# CooperBuffer.net
KiCad netlist of a schematic drawn in EAGLE
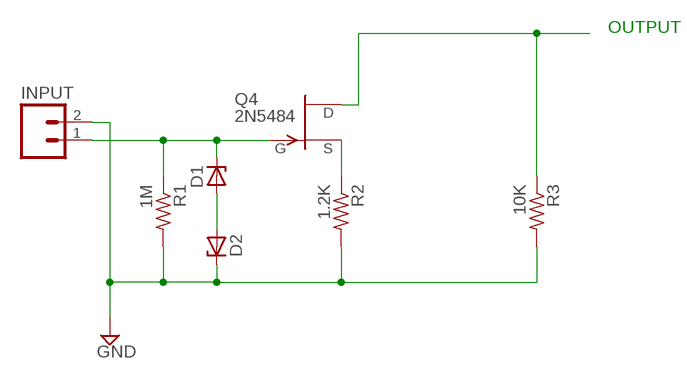
[diagram p0: schematic, sheet 1]

(export (version "E")
  (design (tool "Eeschema 10.0.6"))
  (components
    (comp (ref "D1")
      (value "1N821")
      (footprint "eagle-import:DO35Z10")
      (libsource (lib "eagle-import") (part "1N821"))
    )
    (comp (ref "D2")
      (value "1N821")
      (footprint "eagle-import:DO35Z10")
      (libsource (lib "eagle-import") (part "1N821"))
    )
    (comp (ref "INPUT")
      (value "M02LOCK")
      (footprint "eagle-import:1X02_LOCK")
      (libsource (lib "eagle-import") (part "M02LOCK"))
    )
    (comp (ref "Q4")
      (value "2N5484")
      (footprint "eagle-import:TO92-")
      (libsource (lib "eagle-import") (part "?5482N4"))
    )
    (comp (ref "R1")
      (value "1M")
      (footprint "eagle-import:VMTA55")
      (libsource (lib "eagle-import") (part "R-US_VMTA55"))
    )
    (comp (ref "R2")
      (value "1.2K")
      (footprint "eagle-import:VMTA55")
      (libsource (lib "eagle-import") (part "R-US_VMTA55"))
    )
    (comp (ref "R3")
      (value "10K")
      (footprint "eagle-import:VMTA55")
      (libsource (lib "eagle-import") (part "R-US_VMTA55"))
    )
  )
  (nets
    (net (code "1") (name "GND") (class "Default")
      (node (ref "D2") (pin "C") (pinfunction "C_C") (pintype "passive"))
      (node (ref "INPUT") (pin "2") (pinfunction "2_2") (pintype "passive"))
      (node (ref "R1") (pin "2") (pinfunction "2_2") (pintype "passive"))
      (node (ref "R2") (pin "2") (pinfunction "2_2") (pintype "passive"))
      (node (ref "R3") (pin "2") (pinfunction "2_2") (pintype "passive"))
    )
    (net (code "2") (name "Net-(D1-PadA)") (class "Default")
      (node (ref "D1") (pin "A") (pinfunction "A_A") (pintype "passive"))
      (node (ref "D2") (pin "A") (pinfunction "A_A") (pintype "passive"))
    )
    (net (code "3") (name "Net-(Q4-D)") (class "Default")
      (node (ref "Q4") (pin "3") (pinfunction "D_3") (pintype "passive"))
      (node (ref "R3") (pin "1") (pinfunction "1_1") (pintype "passive"))
    )
    (net (code "4") (name "Net-(Q4-G)") (class "Default")
      (node (ref "D1") (pin "C") (pinfunction "C_C") (pintype "passive"))
      (node (ref "INPUT") (pin "1") (pinfunction "1_1") (pintype "passive"))
      (node (ref "Q4") (pin "1") (pinfunction "G_1") (pintype "passive"))
      (node (ref "R1") (pin "1") (pinfunction "1_1") (pintype "passive"))
    )
    (net (code "5") (name "Net-(Q4-S)") (class "Default")
      (node (ref "Q4") (pin "2") (pinfunction "S_2") (pintype "passive"))
      (node (ref "R2") (pin "1") (pinfunction "1_1") (pintype "passive"))
    )
  )
)
